# door_tx.net
KiCad netlist of a schematic drawn in EAGLE
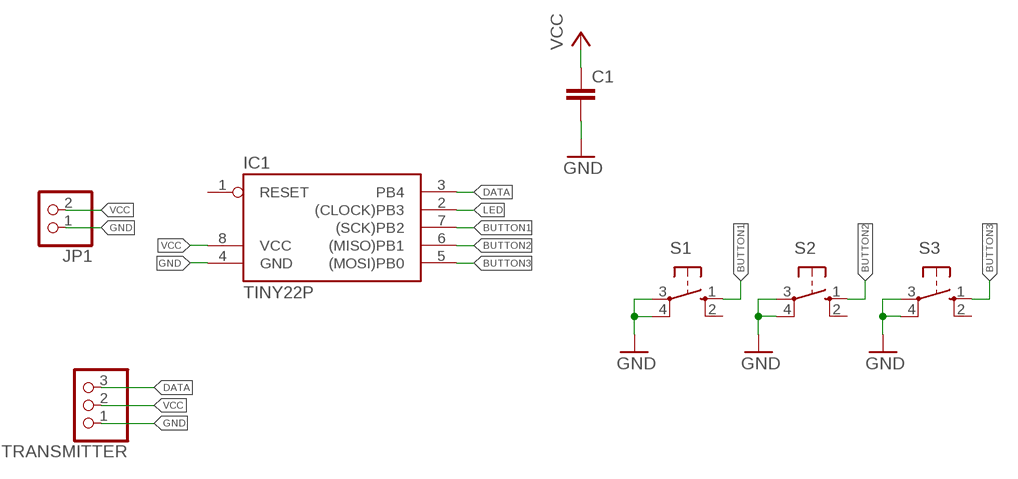
[diagram p0: schematic, sheet 1]

(export (version "E")
  (design (tool "Eeschema 10.0.6"))
  (components
    (comp (ref "C1")
      (value "C-EUC1206K")
      (footprint "eagle-import:C1206K")
      (libsource (lib "eagle-import") (part "C-EUC1206K"))
    )
    (comp (ref "IC1")
      (value "TINY22P")
      (footprint "eagle-import:DIL08")
      (libsource (lib "eagle-import") (part "TINY22P"))
    )
    (comp (ref "JP1")
      (value "PINHD-1X2")
      (footprint "eagle-import:1X02")
      (libsource (lib "eagle-import") (part "PINHD-1X2"))
    )
    (comp (ref "S1")
      (value "10-XX")
      (footprint "eagle-import:B3F-10XX")
      (fields (field (name "MPN") "B3F-1000"))
      (libsource (lib "eagle-import") (part "10-XX"))
    )
    (comp (ref "S2")
      (value "10-XX")
      (footprint "eagle-import:B3F-10XX")
      (fields (field (name "MPN") "B3F-1000"))
      (libsource (lib "eagle-import") (part "10-XX"))
    )
    (comp (ref "S3")
      (value "10-XX")
      (footprint "eagle-import:B3F-10XX")
      (fields (field (name "MPN") "B3F-1000"))
      (libsource (lib "eagle-import") (part "10-XX"))
    )
    (comp (ref "TRANSMITTER")
      (value "PINHD-1X3")
      (footprint "eagle-import:1X03")
      (libsource (lib "eagle-import") (part "PINHD-1X3"))
    )
  )
  (nets
    (net (code "1") (name "BUTTON1") (class "Default")
      (node (ref "IC1") (pin "7") (pinfunction "(SCK)PB2_7") (pintype "bidirectional"))
      (node (ref "S1") (pin "1") (pinfunction "S_1") (pintype "passive"))
    )
    (net (code "2") (name "BUTTON2") (class "Default")
      (node (ref "IC1") (pin "6") (pinfunction "(MISO)PB1_6") (pintype "bidirectional"))
      (node (ref "S2") (pin "1") (pinfunction "S_1") (pintype "passive"))
    )
    (net (code "3") (name "BUTTON3") (class "Default")
      (node (ref "IC1") (pin "5") (pinfunction "(MOSI)PB0_5") (pintype "bidirectional"))
      (node (ref "S3") (pin "1") (pinfunction "S_1") (pintype "passive"))
    )
    (net (code "4") (name "DATA") (class "Default")
      (node (ref "IC1") (pin "3") (pinfunction "PB4_3") (pintype "bidirectional"))
      (node (ref "TRANSMITTER") (pin "3") (pinfunction "3_3") (pintype "passive"))
    )
    (net (code "5") (name "GND") (class "Default")
      (node (ref "C1") (pin "2") (pinfunction "2_2") (pintype "passive"))
      (node (ref "IC1") (pin "4") (pinfunction "GND_4") (pintype "power_in"))
      (node (ref "JP1") (pin "1") (pinfunction "1_1") (pintype "passive"))
      (node (ref "S1") (pin "3") (pinfunction "P_3") (pintype "passive"))
      (node (ref "S1") (pin "4") (pinfunction "P1_4") (pintype "passive"))
      (node (ref "S2") (pin "3") (pinfunction "P_3") (pintype "passive"))
      (node (ref "S2") (pin "4") (pinfunction "P1_4") (pintype "passive"))
      (node (ref "S3") (pin "3") (pinfunction "P_3") (pintype "passive"))
      (node (ref "S3") (pin "4") (pinfunction "P1_4") (pintype "passive"))
      (node (ref "TRANSMITTER") (pin "1") (pinfunction "1_1") (pintype "passive"))
    )
    (net (code "6") (name "LED") (class "Default")
      (node (ref "IC1") (pin "2") (pinfunction "(CLOCK)PB3_2") (pintype "bidirectional"))
    )
    (net (code "7") (name "VCC") (class "Default")
      (node (ref "C1") (pin "1") (pinfunction "1_1") (pintype "passive"))
      (node (ref "IC1") (pin "8") (pinfunction "VCC_8") (pintype "power_in"))
      (node (ref "JP1") (pin "2") (pinfunction "2_2") (pintype "passive"))
      (node (ref "TRANSMITTER") (pin "2") (pinfunction "2_2") (pintype "passive"))
    )
    (net (code "8") (name "unconnected-(IC1-RESET-Pad1)") (class "Default")
      (node (ref "IC1") (pin "1") (pinfunction "RESET_1") (pintype "input"))
    )
    (net (code "9") (name "unconnected-(S1-S1-Pad2)") (class "Default")
      (node (ref "S1") (pin "2") (pinfunction "S1_2") (pintype "passive"))
    )
    (net (code "10") (name "unconnected-(S2-S1-Pad2)") (class "Default")
      (node (ref "S2") (pin "2") (pinfunction "S1_2") (pintype "passive"))
    )
    (net (code "11") (name "unconnected-(S3-S1-Pad2)") (class "Default")
      (node (ref "S3") (pin "2") (pinfunction "S1_2") (pintype "passive"))
    )
  )
)
